# USB-DA-MINI.net
KiCad netlist of a schematic drawn in EAGLE
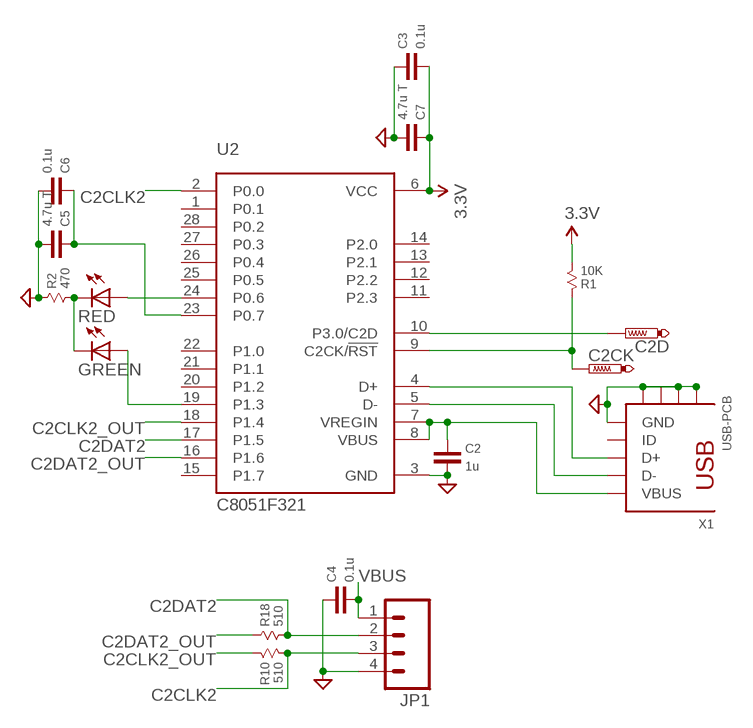
[diagram p0: schematic, sheet 1]

(export (version "E")
  (design (tool "Eeschema 10.0.6"))
  (components
    (comp (ref "C2")
      (value "1u")
      (footprint "eagle-import:0603")
      (libsource (lib "eagle-import") (part "CAP-0603"))
    )
    (comp (ref "C2CK")
      (value "PTR1B1,27")
      (footprint "eagle-import:B1,27")
      (libsource (lib "eagle-import") (part "PTR1B1,27"))
    )
    (comp (ref "C2D")
      (value "PTR1B1,27")
      (footprint "eagle-import:B1,27")
      (libsource (lib "eagle-import") (part "PTR1B1,27"))
    )
    (comp (ref "C3")
      (value "0.1u")
      (footprint "eagle-import:0603")
      (libsource (lib "eagle-import") (part "CAP-0603"))
    )
    (comp (ref "C4")
      (value "0.1u")
      (footprint "eagle-import:0603")
      (libsource (lib "eagle-import") (part "CAP-0603"))
    )
    (comp (ref "C5")
      (value "4.7u T")
      (footprint "eagle-import:0603")
      (libsource (lib "eagle-import") (part "CAP-0603"))
    )
    (comp (ref "C6")
      (value "0.1u")
      (footprint "eagle-import:0603")
      (libsource (lib "eagle-import") (part "CAP-0603"))
    )
    (comp (ref "C7")
      (value "4.7u T")
      (footprint "eagle-import:0603")
      (libsource (lib "eagle-import") (part "CAP-0603"))
    )
    (comp (ref "GREEN")
      (value "LED0603")
      (footprint "eagle-import:LED-0603")
      (libsource (lib "eagle-import") (part "LED0603"))
    )
    (comp (ref "JP1")
      (value "M04PTH")
      (footprint "eagle-import:1X04")
      (libsource (lib "eagle-import") (part "M04PTH"))
    )
    (comp (ref "R1")
      (value "10K")
      (footprint "eagle-import:0603")
      (libsource (lib "eagle-import") (part "RESISTOR-0603"))
    )
    (comp (ref "R2")
      (value "470")
      (footprint "eagle-import:0603")
      (libsource (lib "eagle-import") (part "RESISTOR-0603"))
    )
    (comp (ref "R10")
      (value "510")
      (footprint "eagle-import:0603")
      (libsource (lib "eagle-import") (part "RESISTOR-0603"))
    )
    (comp (ref "R18")
      (value "510")
      (footprint "eagle-import:0603")
      (libsource (lib "eagle-import") (part "RESISTOR-0603"))
    )
    (comp (ref "RED")
      (value "LED0603")
      (footprint "eagle-import:LED-0603")
      (libsource (lib "eagle-import") (part "LED0603"))
    )
    (comp (ref "U2")
      (value "C8051F321")
      (footprint "eagle-import:QFN28-5X5")
      (libsource (lib "eagle-import") (part "C8051F321"))
    )
    (comp (ref "X1")
      (value "USB-PCB")
      (footprint "eagle-import:USB-MINIB")
      (libsource (lib "eagle-import") (part "USB-SMD"))
    )
  )
  (nets
    (net (code "1") (name "/C2CLK2") (class "Default")
      (node (ref "JP1") (pin "3") (pinfunction "3_3") (pintype "passive"))
      (node (ref "R10") (pin "2") (pinfunction "2_2") (pintype "passive"))
      (node (ref "U2") (pin "2") (pinfunction "P0.0_2") (pintype "bidirectional"))
    )
    (net (code "2") (name "/C2CLK2_OUT") (class "Default")
      (node (ref "R10") (pin "1") (pinfunction "1_1") (pintype "passive"))
      (node (ref "U2") (pin "18") (pinfunction "P1.4_18") (pintype "bidirectional"))
    )
    (net (code "3") (name "/C2DAT2") (class "Default")
      (node (ref "JP1") (pin "2") (pinfunction "2_2") (pintype "passive"))
      (node (ref "R18") (pin "2") (pinfunction "2_2") (pintype "passive"))
      (node (ref "U2") (pin "17") (pinfunction "P1.5_17") (pintype "bidirectional"))
    )
    (net (code "4") (name "/C2DAT2_OUT") (class "Default")
      (node (ref "R18") (pin "1") (pinfunction "1_1") (pintype "passive"))
      (node (ref "U2") (pin "16") (pinfunction "P1.6_16") (pintype "bidirectional"))
    )
    (net (code "5") (name "/VBUS") (class "Default")
      (node (ref "C2") (pin "2") (pinfunction "2_2") (pintype "passive"))
      (node (ref "C4") (pin "1") (pinfunction "1_1") (pintype "passive"))
      (node (ref "JP1") (pin "1") (pinfunction "1_1") (pintype "passive"))
      (node (ref "U2") (pin "7") (pinfunction "VREGIN_7") (pintype "bidirectional"))
      (node (ref "U2") (pin "8") (pinfunction "VBUS_8") (pintype "bidirectional"))
      (node (ref "X1") (pin "VBUS") (pinfunction "VBUS_VBUS") (pintype "passive"))
    )
    (net (code "6") (name "3.3V") (class "Default")
      (node (ref "C3") (pin "1") (pinfunction "1_1") (pintype "passive"))
      (node (ref "C7") (pin "2") (pinfunction "2_2") (pintype "passive"))
      (node (ref "R1") (pin "2") (pinfunction "2_2") (pintype "passive"))
      (node (ref "U2") (pin "6") (pinfunction "VCC_6") (pintype "bidirectional"))
    )
    (net (code "7") (name "GND") (class "Default")
      (node (ref "C2") (pin "1") (pinfunction "1_1") (pintype "passive"))
      (node (ref "C3") (pin "2") (pinfunction "2_2") (pintype "passive"))
      (node (ref "C4") (pin "2") (pinfunction "2_2") (pintype "passive"))
      (node (ref "C5") (pin "1") (pinfunction "1_1") (pintype "passive"))
      (node (ref "C6") (pin "1") (pinfunction "1_1") (pintype "passive"))
      (node (ref "C7") (pin "1") (pinfunction "1_1") (pintype "passive"))
      (node (ref "JP1") (pin "4") (pinfunction "4_4") (pintype "passive"))
      (node (ref "R2") (pin "1") (pinfunction "1_1") (pintype "passive"))
      (node (ref "U2") (pin "3") (pinfunction "GND_3") (pintype "power_in"))
      (node (ref "X1") (pin "GND") (pinfunction "GND_GND") (pintype "power_in"))
      (node (ref "X1") (pin "GND@1") (pinfunction "GND_GND@1") (pintype "power_in"))
      (node (ref "X1") (pin "GND@2") (pinfunction "GND_GND@2") (pintype "power_in"))
      (node (ref "X1") (pin "GND@3") (pinfunction "GND_GND@3") (pintype "power_in"))
      (node (ref "X1") (pin "GND@4") (pinfunction "GND_GND@4") (pintype "power_in"))
    )
    (net (code "8") (name "Net-(GREEN-PadC)") (class "Default")
      (node (ref "GREEN") (pin "C") (pinfunction "C_C") (pintype "passive"))
      (node (ref "R2") (pin "2") (pinfunction "2_2") (pintype "passive"))
      (node (ref "RED") (pin "C") (pinfunction "C_C") (pintype "passive"))
    )
    (net (code "9") (name "Net-(U2-C2CK{slash}~{RST})") (class "Default")
      (node (ref "C2CK") (pin "TP") (pinfunction "TP_TP") (pintype "input"))
      (node (ref "R1") (pin "1") (pinfunction "1_1") (pintype "passive"))
      (node (ref "U2") (pin "9") (pinfunction "C2CK/~{RST}_9") (pintype "bidirectional"))
    )
    (net (code "10") (name "Net-(U2-D+)") (class "Default")
      (node (ref "U2") (pin "4") (pinfunction "D+_4") (pintype "bidirectional"))
      (node (ref "X1") (pin "D+") (pinfunction "D+_D+") (pintype "bidirectional"))
    )
    (net (code "11") (name "Net-(U2-D-)") (class "Default")
      (node (ref "U2") (pin "5") (pinfunction "D-_5") (pintype "bidirectional"))
      (node (ref "X1") (pin "D-") (pinfunction "D-_D-") (pintype "bidirectional"))
    )
    (net (code "12") (name "Net-(U2-P0.6)") (class "Default")
      (node (ref "RED") (pin "A") (pinfunction "A_A") (pintype "passive"))
      (node (ref "U2") (pin "24") (pinfunction "P0.6_24") (pintype "bidirectional"))
    )
    (net (code "13") (name "Net-(U2-P0.7)") (class "Default")
      (node (ref "C5") (pin "2") (pinfunction "2_2") (pintype "passive"))
      (node (ref "C6") (pin "2") (pinfunction "2_2") (pintype "passive"))
      (node (ref "U2") (pin "23") (pinfunction "P0.7_23") (pintype "bidirectional"))
    )
    (net (code "14") (name "Net-(U2-P1.3)") (class "Default")
      (node (ref "GREEN") (pin "A") (pinfunction "A_A") (pintype "passive"))
      (node (ref "U2") (pin "19") (pinfunction "P1.3_19") (pintype "bidirectional"))
    )
    (net (code "15") (name "Net-(U2-P3.0{slash}C2D)") (class "Default")
      (node (ref "C2D") (pin "TP") (pinfunction "TP_TP") (pintype "input"))
      (node (ref "U2") (pin "10") (pinfunction "P3.0/C2D_10") (pintype "bidirectional"))
    )
    (net (code "16") (name "unconnected-(U2-P0.1-Pad1)") (class "Default")
      (node (ref "U2") (pin "1") (pinfunction "P0.1_1") (pintype "bidirectional"))
    )
    (net (code "17") (name "unconnected-(U2-P0.2-Pad28)") (class "Default")
      (node (ref "U2") (pin "28") (pinfunction "P0.2_28") (pintype "bidirectional"))
    )
    (net (code "18") (name "unconnected-(U2-P0.3-Pad27)") (class "Default")
      (node (ref "U2") (pin "27") (pinfunction "P0.3_27") (pintype "bidirectional"))
    )
    (net (code "19") (name "unconnected-(U2-P0.4-Pad26)") (class "Default")
      (node (ref "U2") (pin "26") (pinfunction "P0.4_26") (pintype "bidirectional"))
    )
    (net (code "20") (name "unconnected-(U2-P0.5-Pad25)") (class "Default")
      (node (ref "U2") (pin "25") (pinfunction "P0.5_25") (pintype "bidirectional"))
    )
    (net (code "21") (name "unconnected-(U2-P1.0-Pad22)") (class "Default")
      (node (ref "U2") (pin "22") (pinfunction "P1.0_22") (pintype "bidirectional"))
    )
    (net (code "22") (name "unconnected-(U2-P1.1-Pad21)") (class "Default")
      (node (ref "U2") (pin "21") (pinfunction "P1.1_21") (pintype "bidirectional"))
    )
    (net (code "23") (name "unconnected-(U2-P1.2-Pad20)") (class "Default")
      (node (ref "U2") (pin "20") (pinfunction "P1.2_20") (pintype "bidirectional"))
    )
    (net (code "24") (name "unconnected-(U2-P1.7-Pad15)") (class "Default")
      (node (ref "U2") (pin "15") (pinfunction "P1.7_15") (pintype "bidirectional"))
    )
    (net (code "25") (name "unconnected-(U2-P2.0-Pad14)") (class "Default")
      (node (ref "U2") (pin "14") (pinfunction "P2.0_14") (pintype "bidirectional"))
    )
    (net (code "26") (name "unconnected-(U2-P2.1-Pad13)") (class "Default")
      (node (ref "U2") (pin "13") (pinfunction "P2.1_13") (pintype "bidirectional"))
    )
    (net (code "27") (name "unconnected-(U2-P2.2-Pad12)") (class "Default")
      (node (ref "U2") (pin "12") (pinfunction "P2.2_12") (pintype "bidirectional"))
    )
    (net (code "28") (name "unconnected-(U2-P2.3-Pad11)") (class "Default")
      (node (ref "U2") (pin "11") (pinfunction "P2.3_11") (pintype "bidirectional"))
    )
    (net (code "29") (name "unconnected-(X1-PadID)") (class "Default")
      (node (ref "X1") (pin "ID") (pinfunction "ID_ID") (pintype "bidirectional"))
    )
  )
)
